# MEMORY.net
KiCad netlist of a schematic drawn in Altium Designer
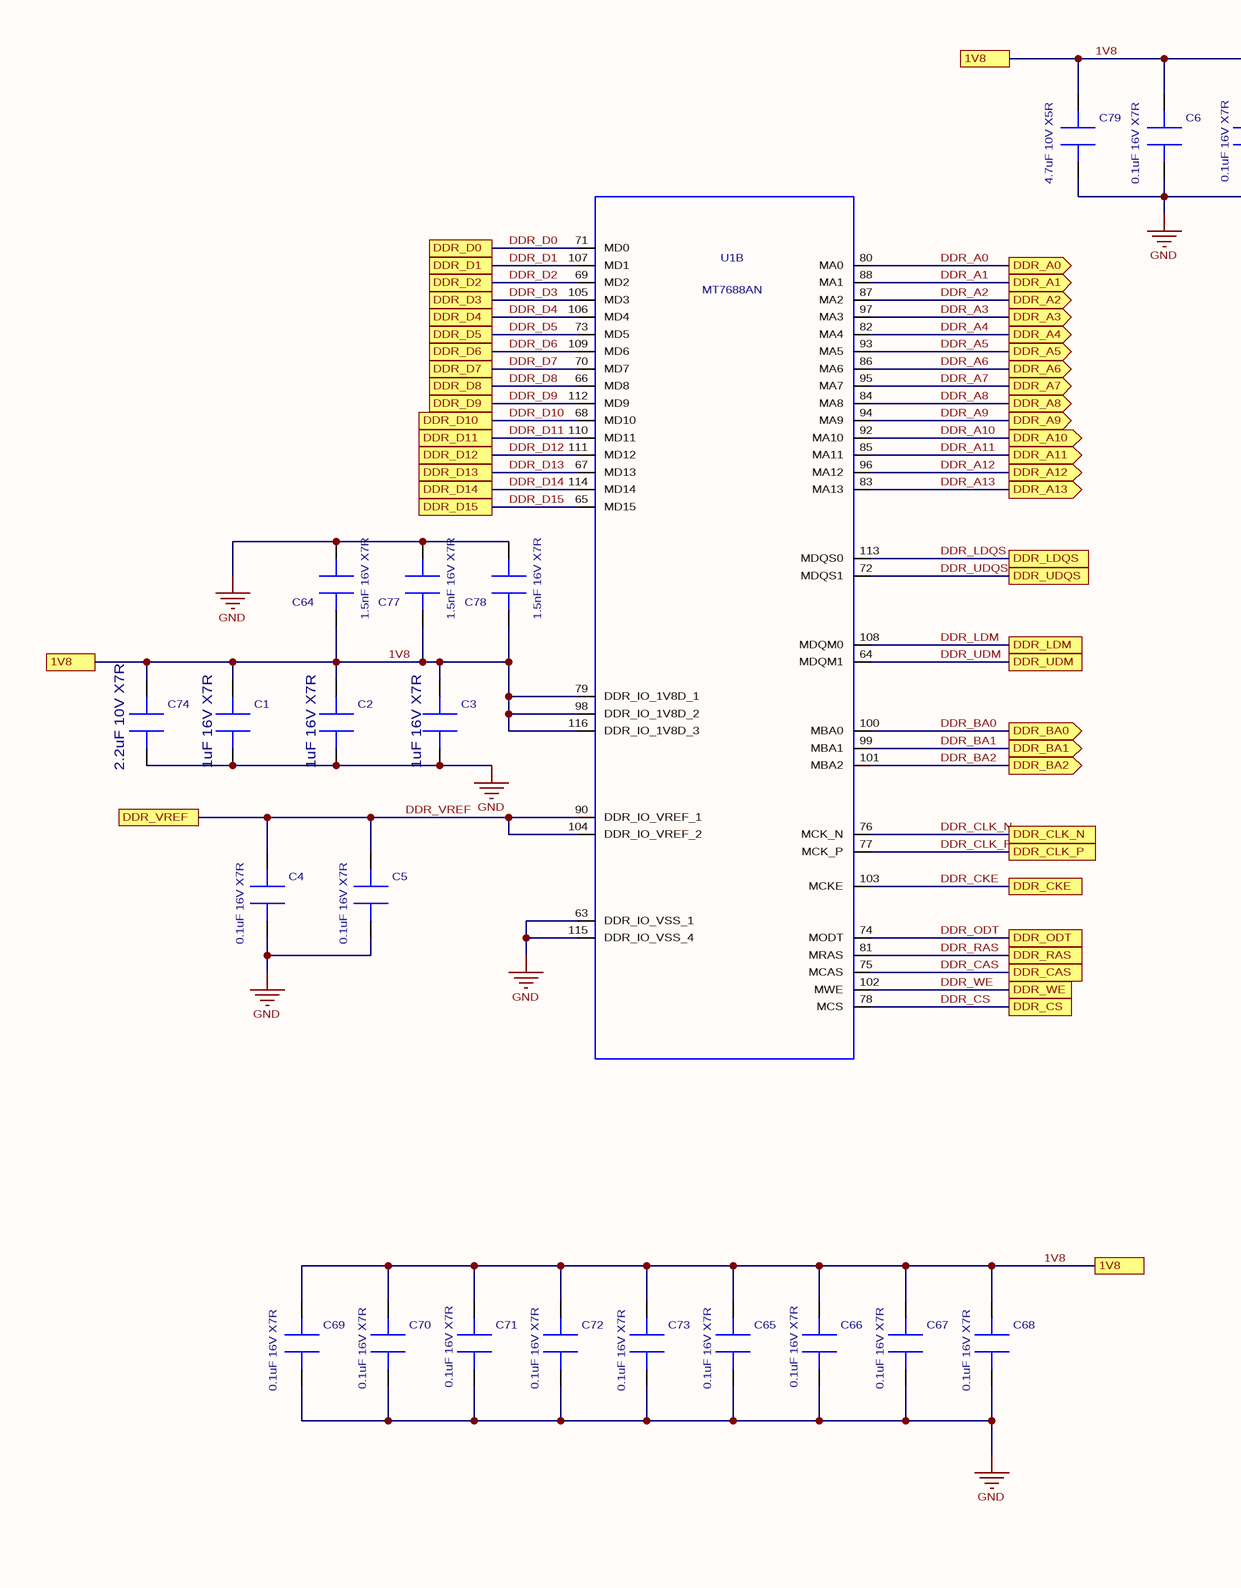
[diagram p0: MEMORY.SchDoc, left]
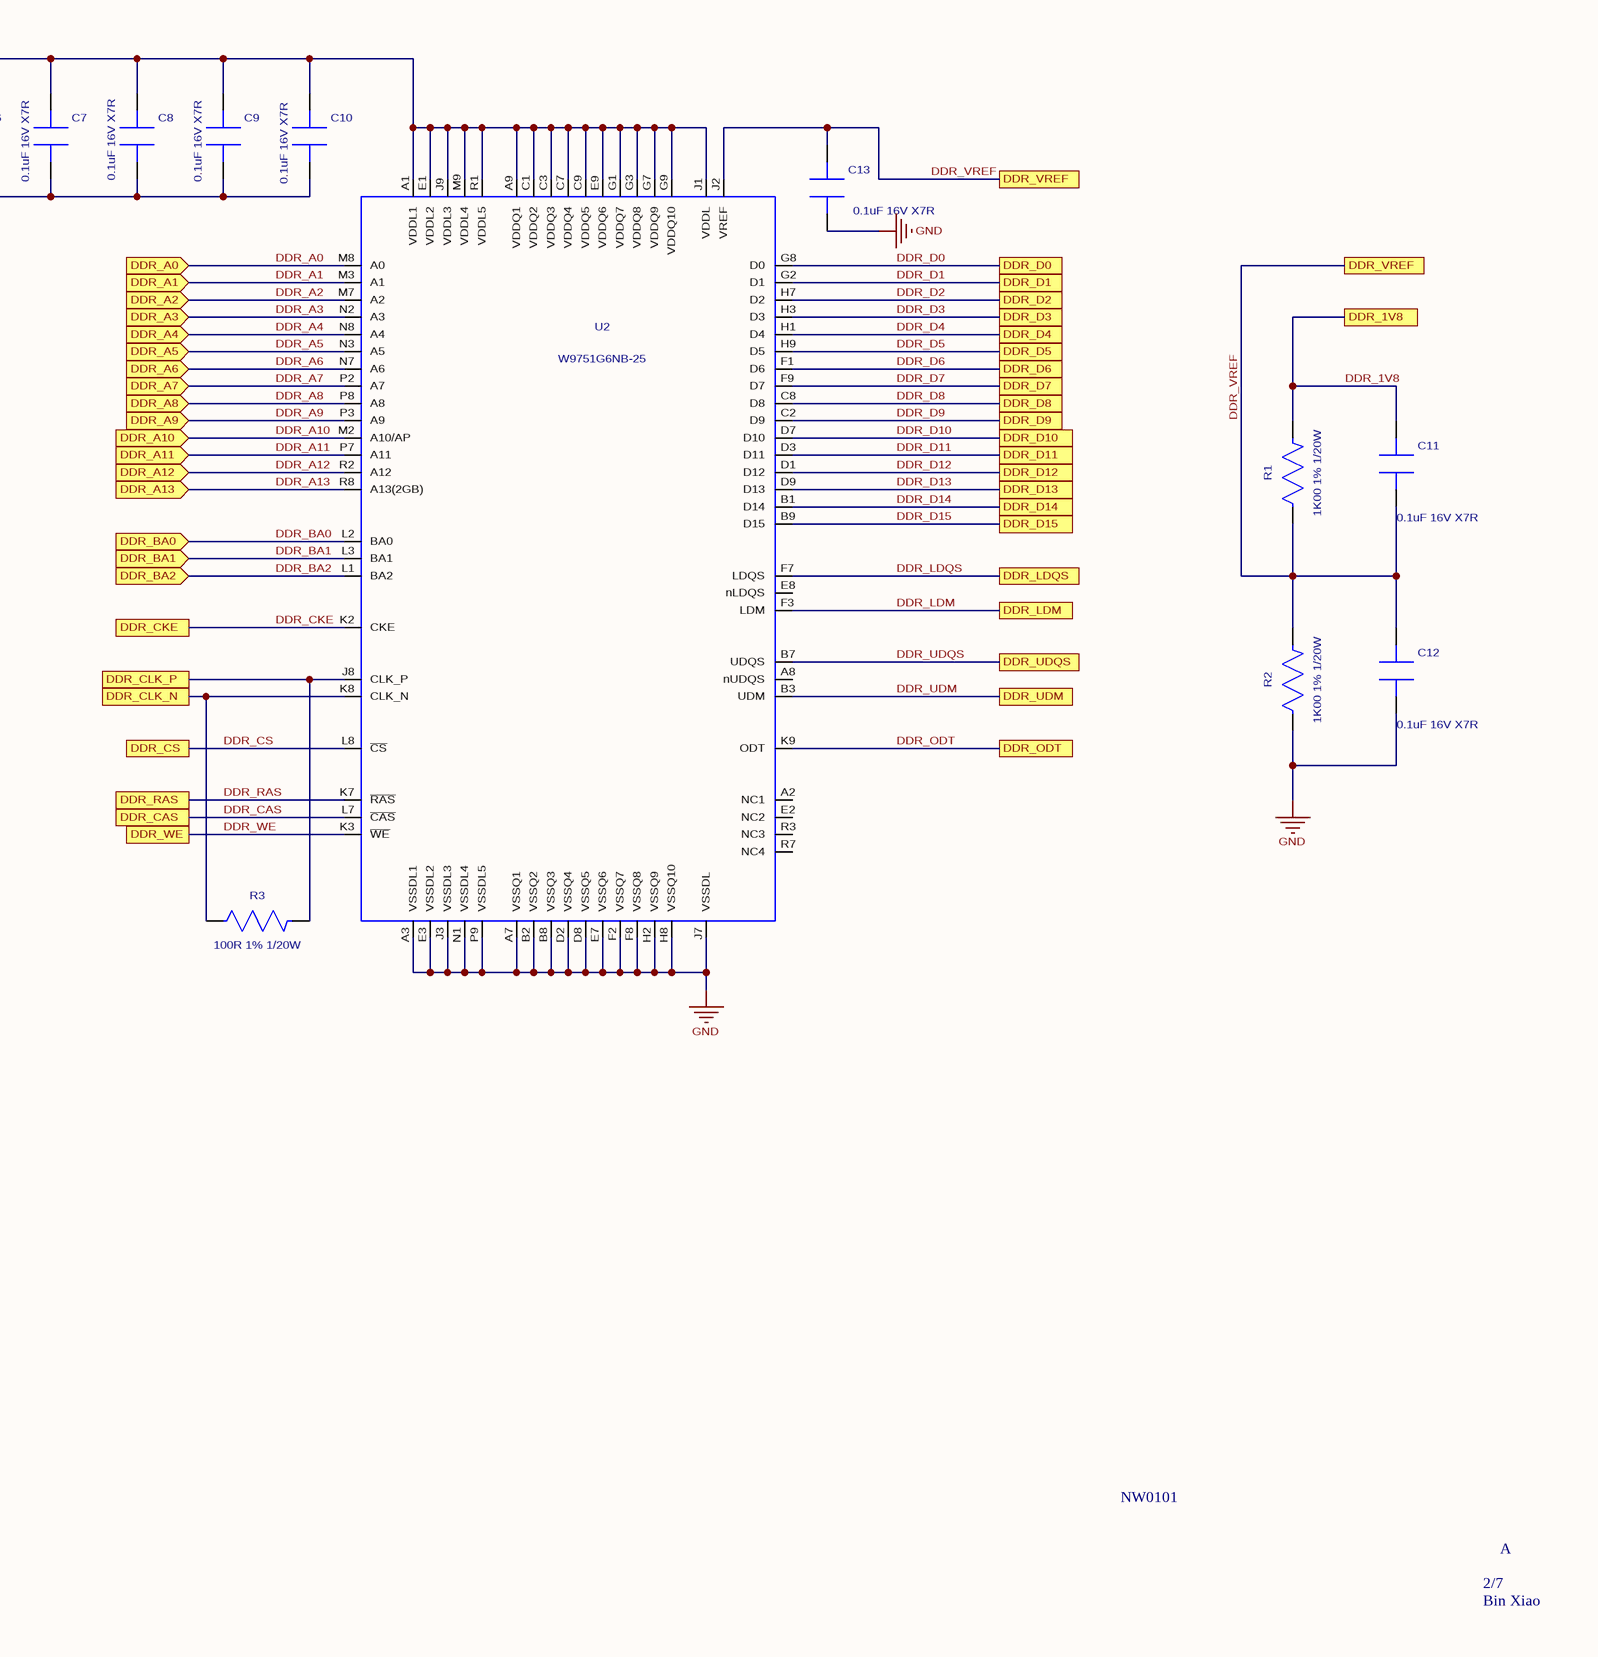
[diagram p1: MEMORY.SchDoc, right]

(export (version "E")
  (design (tool "Eeschema 10.0.6"))
  (components
    (comp (ref "C1")
      (value "1uF 16V X7R")
      (footprint "C0402")
      (description "CAP CER 1UF 6.3V X7R 0402")
      (fields
        (field (name "PART NUMBER") "GRM155R70J105KA12D")
        (field (name "MANUFACTURER") "Murata Electronics")
      )
      (libsource (lib "NetworkModule") (part "CAP0402-105-6.3V-X7R"))
    )
    (comp (ref "C2")
      (value "1uF 16V X7R")
      (footprint "C0402")
      (description "CAP CER 1UF 6.3V X7R 0402")
      (fields
        (field (name "PART NUMBER") "GRM155R70J105KA12D")
        (field (name "MANUFACTURER") "Murata Electronics")
      )
      (libsource (lib "NetworkModule") (part "CAP0402-105-6.3V-X7R"))
    )
    (comp (ref "C3")
      (value "1uF 16V X7R")
      (footprint "C0402")
      (description "CAP CER 1UF 6.3V X7R 0402")
      (fields
        (field (name "PART NUMBER") "GRM155R70J105KA12D")
        (field (name "MANUFACTURER") "Murata Electronics")
      )
      (libsource (lib "NetworkModule") (part "CAP0402-105-6.3V-X7R"))
    )
    (comp (ref "C4")
      (value "0.1uF 16V X7R")
      (footprint "C0201")
      (description "CAP CER 0.1UF 16V X7R 0201")
      (fields
        (field (name "PART NUMBER") "GRM033Z71C104KE14D")
        (field (name "MANUFACTURER") "Murata Electronics")
      )
      (libsource (lib "NetworkModule") (part "CAP0201-104-16V-X7R"))
    )
    (comp (ref "C5")
      (value "0.1uF 16V X7R")
      (footprint "C0201")
      (description "CAP CER 0.1UF 16V X7R 0201")
      (fields
        (field (name "PART NUMBER") "GRM033Z71C104KE14D")
        (field (name "MANUFACTURER") "Murata Electronics")
      )
      (libsource (lib "NetworkModule") (part "CAP0201-104-16V-X7R"))
    )
    (comp (ref "C6")
      (value "0.1uF 16V X7R")
      (footprint "C0201")
      (description "CAP CER 0.1UF 16V X7R 0201")
      (fields
        (field (name "PART NUMBER") "GRM033Z71C104KE14D")
        (field (name "MANUFACTURER") "Murata Electronics")
      )
      (libsource (lib "NetworkModule") (part "CAP0201-104-16V-X7R"))
    )
    (comp (ref "C7")
      (value "0.1uF 16V X7R")
      (footprint "C0201")
      (description "CAP CER 0.1UF 16V X7R 0201")
      (fields
        (field (name "PART NUMBER") "GRM033Z71C104KE14D")
        (field (name "MANUFACTURER") "Murata Electronics")
      )
      (libsource (lib "NetworkModule") (part "CAP0201-104-16V-X7R"))
    )
    (comp (ref "C8")
      (value "0.1uF 16V X7R")
      (footprint "C0201")
      (description "CAP CER 0.1UF 16V X7R 0201")
      (fields
        (field (name "PART NUMBER") "GRM033Z71C104KE14D")
        (field (name "MANUFACTURER") "Murata Electronics")
      )
      (libsource (lib "NetworkModule") (part "CAP0201-104-16V-X7R"))
    )
    (comp (ref "C9")
      (value "0.1uF 16V X7R")
      (footprint "C0201")
      (description "CAP CER 0.1UF 16V X7R 0201")
      (fields
        (field (name "PART NUMBER") "GRM033Z71C104KE14D")
        (field (name "MANUFACTURER") "Murata Electronics")
      )
      (libsource (lib "NetworkModule") (part "CAP0201-104-16V-X7R"))
    )
    (comp (ref "C10")
      (value "0.1uF 16V X7R")
      (footprint "C0201")
      (description "CAP CER 0.1UF 16V X7R 0201")
      (fields
        (field (name "PART NUMBER") "GRM033Z71C104KE14D")
        (field (name "MANUFACTURER") "Murata Electronics")
      )
      (libsource (lib "NetworkModule") (part "CAP0201-104-16V-X7R"))
    )
    (comp (ref "C11")
      (value "0.1uF 16V X7R")
      (footprint "C0201")
      (description "CAP CER 0.1UF 16V X7R 0201")
      (fields
        (field (name "PART NUMBER") "GRM033Z71C104KE14D")
        (field (name "MANUFACTURER") "Murata Electronics")
      )
      (libsource (lib "NetworkModule") (part "CAP0201-104-16V-X7R"))
    )
    (comp (ref "C12")
      (value "0.1uF 16V X7R")
      (footprint "C0201")
      (description "CAP CER 0.1UF 16V X7R 0201")
      (fields
        (field (name "PART NUMBER") "GRM033Z71C104KE14D")
        (field (name "MANUFACTURER") "Murata Electronics")
      )
      (libsource (lib "NetworkModule") (part "CAP0201-104-16V-X7R"))
    )
    (comp (ref "C13")
      (value "0.1uF 16V X7R")
      (footprint "C0201")
      (description "CAP CER 0.1UF 16V X7R 0201")
      (fields
        (field (name "PART NUMBER") "GRM033Z71C104KE14D")
        (field (name "MANUFACTURER") "Murata Electronics")
      )
      (libsource (lib "NetworkModule") (part "CAP0201-104-16V-X7R"))
    )
    (comp (ref "C64")
      (value "1.5nF 16V X7R")
      (footprint "C0201")
      (description "CAP CER 1500PF 16V X7R 0201")
      (fields
        (field (name "PART NUMBER") "CGA1A2X7R1C152K030BA")
        (field (name "MANUFACTURER") "TDK Corporation")
      )
      (libsource (lib "NetworkModule") (part "CAP0201-152-16V-X7R"))
    )
    (comp (ref "C65")
      (value "0.1uF 16V X7R")
      (footprint "C0201")
      (description "CAP CER 0.1UF 16V X7R 0201")
      (fields
        (field (name "PART NUMBER") "GRM033Z71C104KE14D")
        (field (name "MANUFACTURER") "Murata Electronics")
      )
      (libsource (lib "NetworkModule") (part "CAP0201-104-16V-X7R"))
    )
    (comp (ref "C66")
      (value "0.1uF 16V X7R")
      (footprint "C0201")
      (description "CAP CER 0.1UF 16V X7R 0201")
      (fields
        (field (name "PART NUMBER") "GRM033Z71C104KE14D")
        (field (name "MANUFACTURER") "Murata Electronics")
      )
      (libsource (lib "NetworkModule") (part "CAP0201-104-16V-X7R"))
    )
    (comp (ref "C67")
      (value "0.1uF 16V X7R")
      (footprint "C0201")
      (description "CAP CER 0.1UF 16V X7R 0201")
      (fields
        (field (name "PART NUMBER") "GRM033Z71C104KE14D")
        (field (name "MANUFACTURER") "Murata Electronics")
      )
      (libsource (lib "NetworkModule") (part "CAP0201-104-16V-X7R"))
    )
    (comp (ref "C68")
      (value "0.1uF 16V X7R")
      (footprint "C0201")
      (description "CAP CER 0.1UF 16V X7R 0201")
      (fields
        (field (name "PART NUMBER") "GRM033Z71C104KE14D")
        (field (name "MANUFACTURER") "Murata Electronics")
      )
      (libsource (lib "NetworkModule") (part "CAP0201-104-16V-X7R"))
    )
    (comp (ref "C69")
      (value "0.1uF 16V X7R")
      (footprint "C0201")
      (description "CAP CER 0.1UF 16V X7R 0201")
      (fields
        (field (name "PART NUMBER") "GRM033Z71C104KE14D")
        (field (name "MANUFACTURER") "Murata Electronics")
      )
      (libsource (lib "NetworkModule") (part "CAP0201-104-16V-X7R"))
    )
    (comp (ref "C70")
      (value "0.1uF 16V X7R")
      (footprint "C0201")
      (description "CAP CER 0.1UF 16V X7R 0201")
      (fields
        (field (name "PART NUMBER") "GRM033Z71C104KE14D")
        (field (name "MANUFACTURER") "Murata Electronics")
      )
      (libsource (lib "NetworkModule") (part "CAP0201-104-16V-X7R"))
    )
    (comp (ref "C71")
      (value "0.1uF 16V X7R")
      (footprint "C0201")
      (description "CAP CER 0.1UF 16V X7R 0201")
      (fields
        (field (name "PART NUMBER") "GRM033Z71C104KE14D")
        (field (name "MANUFACTURER") "Murata Electronics")
      )
      (libsource (lib "NetworkModule") (part "CAP0201-104-16V-X7R"))
    )
    (comp (ref "C72")
      (value "0.1uF 16V X7R")
      (footprint "C0201")
      (description "CAP CER 0.1UF 16V X7R 0201")
      (fields
        (field (name "PART NUMBER") "GRM033Z71C104KE14D")
        (field (name "MANUFACTURER") "Murata Electronics")
      )
      (libsource (lib "NetworkModule") (part "CAP0201-104-16V-X7R"))
    )
    (comp (ref "C73")
      (value "0.1uF 16V X7R")
      (footprint "C0201")
      (description "CAP CER 0.1UF 16V X7R 0201")
      (fields
        (field (name "PART NUMBER") "GRM033Z71C104KE14D")
        (field (name "MANUFACTURER") "Murata Electronics")
      )
      (libsource (lib "NetworkModule") (part "CAP0201-104-16V-X7R"))
    )
    (comp (ref "C74")
      (value "2.2uF 10V X7R")
      (footprint "C0402")
      (description "CAP CER 2.2UF 10V X7R 0402")
      (fields
        (field (name "PART NUMBER") "GRM155Z71A225KE01D")
        (field (name "MANUFACTURER") "Murata Electronics")
      )
      (libsource (lib "NetworkModule") (part "CAP0402-225-6.3V-X7R"))
    )
    (comp (ref "C77")
      (value "1.5nF 16V X7R")
      (footprint "C0201")
      (description "CAP CER 1500PF 16V X7R 0201")
      (fields
        (field (name "PART NUMBER") "CGA1A2X7R1C152K030BA")
        (field (name "MANUFACTURER") "TDK Corporation")
      )
      (libsource (lib "NetworkModule") (part "CAP0201-152-16V-X7R"))
    )
    (comp (ref "C78")
      (value "1.5nF 16V X7R")
      (footprint "C0201")
      (description "CAP CER 1500PF 16V X7R 0201")
      (fields
        (field (name "PART NUMBER") "CGA1A2X7R1C152K030BA")
        (field (name "MANUFACTURER") "TDK Corporation")
      )
      (libsource (lib "NetworkModule") (part "CAP0201-152-16V-X7R"))
    )
    (comp (ref "C79")
      (value "4.7uF 10V X5R")
      (footprint "C0402")
      (description "CAP CER 4.7UF 10V X5R 0402")
      (fields
        (field (name "PART NUMBER") "CL05A475MP5NRNC")
        (field (name "MANUFACTURER") "Samsung Electro-Mechanics")
      )
      (libsource (lib "NetworkModule") (part "CAP0402-475-10V-X5R"))
    )
    (comp (ref "R1")
      (value "1K00 1% 1/20W")
      (footprint "R0201")
      (description "RES 1K OHM 1% 1/20W 0201")
      (fields
        (field (name "PART NUMBER") "RMCF0201FT1K00")
        (field (name "MANUFACTURER") "Stackpole Electronics Inc")
      )
      (libsource (lib "NetworkModule") (part "RES0201-1K00"))
    )
    (comp (ref "R2")
      (value "1K00 1% 1/20W")
      (footprint "R0201")
      (description "RES 1K OHM 1% 1/20W 0201")
      (fields
        (field (name "PART NUMBER") "RMCF0201FT1K00")
        (field (name "MANUFACTURER") "Stackpole Electronics Inc")
      )
      (libsource (lib "NetworkModule") (part "RES0201-1K00"))
    )
    (comp (ref "R3")
      (value "100R 1% 1/20W")
      (footprint "R0201")
      (description "RES 100 OHM 1% 1/20W 0201")
      (fields (field (name "MANUFACTURER") "Yageo") (field (name "PART NUMBER") "RC0201FR-07100RL"))
      (libsource (lib "NetworkModule") (part "RES0201-100R"))
    )
    (comp (ref "U1")
      (value "MT7688AN")
      (footprint "DR-QFN-128")
      (description "580Mhz 32bits Networking Processor")
      (fields (field (name "MANUFACTURER") "MediaTek Inc"))
      (libsource (lib "*") (part "MT7688AN"))
    )
    (comp (ref "U2")
      (value "W9751G6NB-25")
      (footprint "TWBGA-84_8X12P5_ISI")
      (description "IC DRAM 512MBIT PARALLEL 84VFBGA")
      (fields (field (name "MANUFACTURER") "Winbond Electronics"))
      (libsource (lib "NetworkModule") (part "W9751G6NB-25"))
    )
  )
  (nets
    (net (code "1") (name "/1V8") (class "Default")
      (node (ref "C1") (pin "1") (pinfunction "1_1") (pintype "passive"))
      (node (ref "C10") (pin "1") (pinfunction "1_1") (pintype "passive"))
      (node (ref "C2") (pin "1") (pinfunction "1_1") (pintype "passive"))
      (node (ref "C3") (pin "1") (pinfunction "1_1") (pintype "passive"))
      (node (ref "C6") (pin "1") (pinfunction "1_1") (pintype "passive"))
      (node (ref "C64") (pin "1") (pinfunction "1_1") (pintype "passive"))
      (node (ref "C65") (pin "1") (pinfunction "1_1") (pintype "passive"))
      (node (ref "C66") (pin "1") (pinfunction "1_1") (pintype "passive"))
      (node (ref "C67") (pin "1") (pinfunction "1_1") (pintype "passive"))
      (node (ref "C68") (pin "1") (pinfunction "1_1") (pintype "passive"))
      (node (ref "C69") (pin "1") (pinfunction "1_1") (pintype "passive"))
      (node (ref "C7") (pin "1") (pinfunction "1_1") (pintype "passive"))
      (node (ref "C70") (pin "1") (pinfunction "1_1") (pintype "passive"))
      (node (ref "C71") (pin "1") (pinfunction "1_1") (pintype "passive"))
      (node (ref "C72") (pin "1") (pinfunction "1_1") (pintype "passive"))
      (node (ref "C73") (pin "1") (pinfunction "1_1") (pintype "passive"))
      (node (ref "C74") (pin "1") (pinfunction "1_1") (pintype "passive"))
      (node (ref "C77") (pin "1") (pinfunction "1_1") (pintype "passive"))
      (node (ref "C78") (pin "1") (pinfunction "1_1") (pintype "passive"))
      (node (ref "C79") (pin "1") (pinfunction "1_1") (pintype "passive"))
      (node (ref "C8") (pin "1") (pinfunction "1_1") (pintype "passive"))
      (node (ref "C9") (pin "1") (pinfunction "1_1") (pintype "passive"))
      (node (ref "U1") (pin "116") (pinfunction "DDR_IO_1V8D_3_116") (pintype "passive"))
      (node (ref "U1") (pin "79") (pinfunction "DDR_IO_1V8D_1_79") (pintype "passive"))
      (node (ref "U1") (pin "98") (pinfunction "DDR_IO_1V8D_2_98") (pintype "passive"))
      (node (ref "U2") (pin "A1") (pinfunction "VDDL1_A1") (pintype "passive"))
      (node (ref "U2") (pin "A9") (pinfunction "VDDQ1_A9") (pintype "passive"))
      (node (ref "U2") (pin "C1") (pinfunction "VDDQ2_C1") (pintype "passive"))
      (node (ref "U2") (pin "C3") (pinfunction "VDDQ3_C3") (pintype "passive"))
      (node (ref "U2") (pin "C7") (pinfunction "VDDQ4_C7") (pintype "passive"))
      (node (ref "U2") (pin "C9") (pinfunction "VDDQ5_C9") (pintype "passive"))
      (node (ref "U2") (pin "E1") (pinfunction "VDDL2_E1") (pintype "passive"))
      (node (ref "U2") (pin "E9") (pinfunction "VDDQ6_E9") (pintype "passive"))
      (node (ref "U2") (pin "G1") (pinfunction "VDDQ7_G1") (pintype "passive"))
      (node (ref "U2") (pin "G3") (pinfunction "VDDQ8_G3") (pintype "passive"))
      (node (ref "U2") (pin "G7") (pinfunction "VDDQ9_G7") (pintype "passive"))
      (node (ref "U2") (pin "G9") (pinfunction "VDDQ10_G9") (pintype "passive"))
      (node (ref "U2") (pin "J1") (pinfunction "VDDL_J1") (pintype "passive"))
      (node (ref "U2") (pin "J9") (pinfunction "VDDL3_J9") (pintype "passive"))
      (node (ref "U2") (pin "M9") (pinfunction "VDDL4_M9") (pintype "passive"))
      (node (ref "U2") (pin "R1") (pinfunction "VDDL5_R1") (pintype "passive"))
    )
    (net (code "2") (name "/DDR_1V8") (class "Default")
      (node (ref "C11") (pin "1") (pinfunction "1_1") (pintype "passive"))
      (node (ref "R1") (pin "2") (pinfunction "2_2") (pintype "passive"))
    )
    (net (code "3") (name "/DDR_A0") (class "Default")
      (node (ref "U1") (pin "80") (pinfunction "MA0_80") (pintype "passive"))
      (node (ref "U2") (pin "M8") (pinfunction "A0_M8") (pintype "passive"))
    )
    (net (code "4") (name "/DDR_A1") (class "Default")
      (node (ref "U1") (pin "88") (pinfunction "MA1_88") (pintype "passive"))
      (node (ref "U2") (pin "M3") (pinfunction "A1_M3") (pintype "passive"))
    )
    (net (code "5") (name "/DDR_A2") (class "Default")
      (node (ref "U1") (pin "87") (pinfunction "MA2_87") (pintype "passive"))
      (node (ref "U2") (pin "M7") (pinfunction "A2_M7") (pintype "passive"))
    )
    (net (code "6") (name "/DDR_A3") (class "Default")
      (node (ref "U1") (pin "97") (pinfunction "MA3_97") (pintype "passive"))
      (node (ref "U2") (pin "N2") (pinfunction "A3_N2") (pintype "passive"))
    )
    (net (code "7") (name "/DDR_A4") (class "Default")
      (node (ref "U1") (pin "82") (pinfunction "MA4_82") (pintype "passive"))
      (node (ref "U2") (pin "N8") (pinfunction "A4_N8") (pintype "passive"))
    )
    (net (code "8") (name "/DDR_A5") (class "Default")
      (node (ref "U1") (pin "93") (pinfunction "MA5_93") (pintype "passive"))
      (node (ref "U2") (pin "N3") (pinfunction "A5_N3") (pintype "passive"))
    )
    (net (code "9") (name "/DDR_A6") (class "Default")
      (node (ref "U1") (pin "86") (pinfunction "MA6_86") (pintype "passive"))
      (node (ref "U2") (pin "N7") (pinfunction "A6_N7") (pintype "passive"))
    )
    (net (code "10") (name "/DDR_A7") (class "Default")
      (node (ref "U1") (pin "95") (pinfunction "MA7_95") (pintype "passive"))
      (node (ref "U2") (pin "P2") (pinfunction "A7_P2") (pintype "passive"))
    )
    (net (code "11") (name "/DDR_A8") (class "Default")
      (node (ref "U1") (pin "84") (pinfunction "MA8_84") (pintype "passive"))
      (node (ref "U2") (pin "P8") (pinfunction "A8_P8") (pintype "passive"))
    )
    (net (code "12") (name "/DDR_A9") (class "Default")
      (node (ref "U1") (pin "94") (pinfunction "MA9_94") (pintype "passive"))
      (node (ref "U2") (pin "P3") (pinfunction "A9_P3") (pintype "passive"))
    )
    (net (code "13") (name "/DDR_A10") (class "Default")
      (node (ref "U1") (pin "92") (pinfunction "MA10_92") (pintype "passive"))
      (node (ref "U2") (pin "M2") (pinfunction "A10/AP_M2") (pintype "passive"))
    )
    (net (code "14") (name "/DDR_A11") (class "Default")
      (node (ref "U1") (pin "85") (pinfunction "MA11_85") (pintype "passive"))
      (node (ref "U2") (pin "P7") (pinfunction "A11_P7") (pintype "passive"))
    )
    (net (code "15") (name "/DDR_A12") (class "Default")
      (node (ref "U1") (pin "96") (pinfunction "MA12_96") (pintype "passive"))
      (node (ref "U2") (pin "R2") (pinfunction "A12_R2") (pintype "passive"))
    )
    (net (code "16") (name "/DDR_A13") (class "Default")
      (node (ref "U1") (pin "83") (pinfunction "MA13_83") (pintype "passive"))
      (node (ref "U2") (pin "R8") (pinfunction "A13(2GB)_R8") (pintype "passive"))
    )
    (net (code "17") (name "/DDR_BA0") (class "Default")
      (node (ref "U1") (pin "100") (pinfunction "MBA0_100") (pintype "passive"))
      (node (ref "U2") (pin "L2") (pinfunction "BA0_L2") (pintype "passive"))
    )
    (net (code "18") (name "/DDR_BA1") (class "Default")
      (node (ref "U1") (pin "99") (pinfunction "MBA1_99") (pintype "passive"))
      (node (ref "U2") (pin "L3") (pinfunction "BA1_L3") (pintype "passive"))
    )
    (net (code "19") (name "/DDR_BA2") (class "Default")
      (node (ref "U1") (pin "101") (pinfunction "MBA2_101") (pintype "passive"))
      (node (ref "U2") (pin "L1") (pinfunction "BA2_L1") (pintype "passive"))
    )
    (net (code "20") (name "/DDR_CAS") (class "Default")
      (node (ref "U1") (pin "75") (pinfunction "MCAS_75") (pintype "passive"))
      (node (ref "U2") (pin "L7") (pinfunction "CAS_L7") (pintype "passive"))
    )
    (net (code "21") (name "/DDR_CKE") (class "Default")
      (node (ref "U1") (pin "103") (pinfunction "MCKE_103") (pintype "passive"))
      (node (ref "U2") (pin "K2") (pinfunction "CKE_K2") (pintype "passive"))
    )
    (net (code "22") (name "/DDR_CLK_N") (class "Default")
      (node (ref "R3") (pin "1") (pinfunction "1_1") (pintype "passive"))
      (node (ref "U1") (pin "76") (pinfunction "MCK_N_76") (pintype "passive"))
      (node (ref "U2") (pin "K8") (pinfunction "CLK_N_K8") (pintype "passive"))
    )
    (net (code "23") (name "/DDR_CLK_P") (class "Default")
      (node (ref "R3") (pin "2") (pinfunction "2_2") (pintype "passive"))
      (node (ref "U1") (pin "77") (pinfunction "MCK_P_77") (pintype "passive"))
      (node (ref "U2") (pin "J8") (pinfunction "CLK_P_J8") (pintype "passive"))
    )
    (net (code "24") (name "/DDR_CS") (class "Default")
      (node (ref "U1") (pin "78") (pinfunction "MCS_78") (pintype "passive"))
      (node (ref "U2") (pin "L8") (pinfunction "CS_L8") (pintype "passive"))
    )
    (net (code "25") (name "/DDR_D0") (class "Default")
      (node (ref "U1") (pin "71") (pinfunction "MD0_71") (pintype "passive"))
      (node (ref "U2") (pin "G8") (pinfunction "D0_G8") (pintype "passive"))
    )
    (net (code "26") (name "/DDR_D1") (class "Default")
      (node (ref "U1") (pin "107") (pinfunction "MD1_107") (pintype "passive"))
      (node (ref "U2") (pin "G2") (pinfunction "D1_G2") (pintype "passive"))
    )
    (net (code "27") (name "/DDR_D2") (class "Default")
      (node (ref "U1") (pin "69") (pinfunction "MD2_69") (pintype "passive"))
      (node (ref "U2") (pin "H7") (pinfunction "D2_H7") (pintype "passive"))
    )
    (net (code "28") (name "/DDR_D3") (class "Default")
      (node (ref "U1") (pin "105") (pinfunction "MD3_105") (pintype "passive"))
      (node (ref "U2") (pin "H3") (pinfunction "D3_H3") (pintype "passive"))
    )
    (net (code "29") (name "/DDR_D4") (class "Default")
      (node (ref "U1") (pin "106") (pinfunction "MD4_106") (pintype "passive"))
      (node (ref "U2") (pin "H1") (pinfunction "D4_H1") (pintype "passive"))
    )
    (net (code "30") (name "/DDR_D5") (class "Default")
      (node (ref "U1") (pin "73") (pinfunction "MD5_73") (pintype "passive"))
      (node (ref "U2") (pin "H9") (pinfunction "D5_H9") (pintype "passive"))
    )
    (net (code "31") (name "/DDR_D6") (class "Default")
      (node (ref "U1") (pin "109") (pinfunction "MD6_109") (pintype "passive"))
      (node (ref "U2") (pin "F1") (pinfunction "D6_F1") (pintype "passive"))
    )
    (net (code "32") (name "/DDR_D7") (class "Default")
      (node (ref "U1") (pin "70") (pinfunction "MD7_70") (pintype "passive"))
      (node (ref "U2") (pin "F9") (pinfunction "D7_F9") (pintype "passive"))
    )
    (net (code "33") (name "/DDR_D8") (class "Default")
      (node (ref "U1") (pin "66") (pinfunction "MD8_66") (pintype "passive"))
      (node (ref "U2") (pin "C8") (pinfunction "D8_C8") (pintype "passive"))
    )
    (net (code "34") (name "/DDR_D9") (class "Default")
      (node (ref "U1") (pin "112") (pinfunction "MD9_112") (pintype "passive"))
      (node (ref "U2") (pin "C2") (pinfunction "D9_C2") (pintype "passive"))
    )
    (net (code "35") (name "/DDR_D10") (class "Default")
      (node (ref "U1") (pin "68") (pinfunction "MD10_68") (pintype "passive"))
      (node (ref "U2") (pin "D7") (pinfunction "D10_D7") (pintype "passive"))
    )
    (net (code "36") (name "/DDR_D11") (class "Default")
      (node (ref "U1") (pin "110") (pinfunction "MD11_110") (pintype "passive"))
      (node (ref "U2") (pin "D3") (pinfunction "D11_D3") (pintype "passive"))
    )
    (net (code "37") (name "/DDR_D12") (class "Default")
      (node (ref "U1") (pin "111") (pinfunction "MD12_111") (pintype "passive"))
      (node (ref "U2") (pin "D1") (pinfunction "D12_D1") (pintype "passive"))
    )
    (net (code "38") (name "/DDR_D13") (class "Default")
      (node (ref "U1") (pin "67") (pinfunction "MD13_67") (pintype "passive"))
      (node (ref "U2") (pin "D9") (pinfunction "D13_D9") (pintype "passive"))
    )
    (net (code "39") (name "/DDR_D14") (class "Default")
      (node (ref "U1") (pin "114") (pinfunction "MD14_114") (pintype "passive"))
      (node (ref "U2") (pin "B1") (pinfunction "D14_B1") (pintype "passive"))
    )
    (net (code "40") (name "/DDR_D15") (class "Default")
      (node (ref "U1") (pin "65") (pinfunction "MD15_65") (pintype "passive"))
      (node (ref "U2") (pin "B9") (pinfunction "D15_B9") (pintype "passive"))
    )
    (net (code "41") (name "/DDR_LDM") (class "Default")
      (node (ref "U1") (pin "108") (pinfunction "MDQM0_108") (pintype "passive"))
      (node (ref "U2") (pin "F3") (pinfunction "LDM_F3") (pintype "passive"))
    )
    (net (code "42") (name "/DDR_LDQS") (class "Default")
      (node (ref "U1") (pin "113") (pinfunction "MDQS0_113") (pintype "passive"))
      (node (ref "U2") (pin "F7") (pinfunction "LDQS_F7") (pintype "passive"))
    )
    (net (code "43") (name "/DDR_ODT") (class "Default")
      (node (ref "U1") (pin "74") (pinfunction "MODT_74") (pintype "passive"))
      (node (ref "U2") (pin "K9") (pinfunction "ODT_K9") (pintype "passive"))
    )
    (net (code "44") (name "/DDR_RAS") (class "Default")
      (node (ref "U1") (pin "81") (pinfunction "MRAS_81") (pintype "passive"))
      (node (ref "U2") (pin "K7") (pinfunction "RAS_K7") (pintype "passive"))
    )
    (net (code "45") (name "/DDR_UDM") (class "Default")
      (node (ref "U1") (pin "64") (pinfunction "MDQM1_64") (pintype "passive"))
      (node (ref "U2") (pin "B3") (pinfunction "UDM_B3") (pintype "passive"))
    )
    (net (code "46") (name "/DDR_UDQS") (class "Default")
      (node (ref "U1") (pin "72") (pinfunction "MDQS1_72") (pintype "passive"))
      (node (ref "U2") (pin "B7") (pinfunction "UDQS_B7") (pintype "passive"))
    )
    (net (code "47") (name "/DDR_VREF") (class "Default")
      (node (ref "C11") (pin "2") (pinfunction "2_2") (pintype "passive"))
      (node (ref "C12") (pin "1") (pinfunction "1_1") (pintype "passive"))
      (node (ref "C13") (pin "1") (pinfunction "1_1") (pintype "passive"))
      (node (ref "C4") (pin "1") (pinfunction "1_1") (pintype "passive"))
      (node (ref "C5") (pin "1") (pinfunction "1_1") (pintype "passive"))
      (node (ref "R1") (pin "1") (pinfunction "1_1") (pintype "passive"))
      (node (ref "R2") (pin "2") (pinfunction "2_2") (pintype "passive"))
      (node (ref "U1") (pin "104") (pinfunction "DDR_IO_VREF_2_104") (pintype "passive"))
      (node (ref "U1") (pin "90") (pinfunction "DDR_IO_VREF_1_90") (pintype "passive"))
      (node (ref "U2") (pin "J2") (pinfunction "VREF_J2") (pintype "passive"))
    )
    (net (code "48") (name "/DDR_WE") (class "Default")
      (node (ref "U1") (pin "102") (pinfunction "MWE_102") (pintype "passive"))
      (node (ref "U2") (pin "K3") (pinfunction "WE_K3") (pintype "passive"))
    )
    (net (code "49") (name "GND") (class "Default")
      (node (ref "C1") (pin "2") (pinfunction "2_2") (pintype "passive"))
      (node (ref "C10") (pin "2") (pinfunction "2_2") (pintype "passive"))
      (node (ref "C12") (pin "2") (pinfunction "2_2") (pintype "passive"))
      (node (ref "C13") (pin "2") (pinfunction "2_2") (pintype "passive"))
      (node (ref "C2") (pin "2") (pinfunction "2_2") (pintype "passive"))
      (node (ref "C3") (pin "2") (pinfunction "2_2") (pintype "passive"))
      (node (ref "C4") (pin "2") (pinfunction "2_2") (pintype "passive"))
      (node (ref "C5") (pin "2") (pinfunction "2_2") (pintype "passive"))
      (node (ref "C6") (pin "2") (pinfunction "2_2") (pintype "passive"))
      (node (ref "C64") (pin "2") (pinfunction "2_2") (pintype "passive"))
      (node (ref "C65") (pin "2") (pinfunction "2_2") (pintype "passive"))
      (node (ref "C66") (pin "2") (pinfunction "2_2") (pintype "passive"))
      (node (ref "C67") (pin "2") (pinfunction "2_2") (pintype "passive"))
      (node (ref "C68") (pin "2") (pinfunction "2_2") (pintype "passive"))
      (node (ref "C69") (pin "2") (pinfunction "2_2") (pintype "passive"))
      (node (ref "C7") (pin "2") (pinfunction "2_2") (pintype "passive"))
      (node (ref "C70") (pin "2") (pinfunction "2_2") (pintype "passive"))
      (node (ref "C71") (pin "2") (pinfunction "2_2") (pintype "passive"))
      (node (ref "C72") (pin "2") (pinfunction "2_2") (pintype "passive"))
      (node (ref "C73") (pin "2") (pinfunction "2_2") (pintype "passive"))
      (node (ref "C74") (pin "2") (pinfunction "2_2") (pintype "passive"))
      (node (ref "C77") (pin "2") (pinfunction "2_2") (pintype "passive"))
      (node (ref "C78") (pin "2") (pinfunction "2_2") (pintype "passive"))
      (node (ref "C79") (pin "2") (pinfunction "2_2") (pintype "passive"))
      (node (ref "C8") (pin "2") (pinfunction "2_2") (pintype "passive"))
      (node (ref "C9") (pin "2") (pinfunction "2_2") (pintype "passive"))
      (node (ref "R2") (pin "1") (pinfunction "1_1") (pintype "passive"))
      (node (ref "U1") (pin "115") (pinfunction "DDR_IO_VSS_4_115") (pintype "passive"))
      (node (ref "U1") (pin "63") (pinfunction "DDR_IO_VSS_1_63") (pintype "passive"))
      (node (ref "U2") (pin "A3") (pinfunction "VSSDL1_A3") (pintype "passive"))
      (node (ref "U2") (pin "A7") (pinfunction "VSSQ1_A7") (pintype "passive"))
      (node (ref "U2") (pin "B2") (pinfunction "VSSQ2_B2") (pintype "passive"))
      (node (ref "U2") (pin "B8") (pinfunction "VSSQ3_B8") (pintype "passive"))
      (node (ref "U2") (pin "D2") (pinfunction "VSSQ4_D2") (pintype "passive"))
      (node (ref "U2") (pin "D8") (pinfunction "VSSQ5_D8") (pintype "passive"))
      (node (ref "U2") (pin "E3") (pinfunction "VSSDL2_E3") (pintype "passive"))
      (node (ref "U2") (pin "E7") (pinfunction "VSSQ6_E7") (pintype "passive"))
      (node (ref "U2") (pin "F2") (pinfunction "VSSQ7_F2") (pintype "passive"))
      (node (ref "U2") (pin "F8") (pinfunction "VSSQ8_F8") (pintype "passive"))
      (node (ref "U2") (pin "H2") (pinfunction "VSSQ9_H2") (pintype "passive"))
      (node (ref "U2") (pin "H8") (pinfunction "VSSQ10_H8") (pintype "passive"))
      (node (ref "U2") (pin "J3") (pinfunction "VSSDL3_J3") (pintype "passive"))
      (node (ref "U2") (pin "J7") (pinfunction "VSSDL_J7") (pintype "passive"))
      (node (ref "U2") (pin "N1") (pinfunction "VSSDL4_N1") (pintype "passive"))
      (node (ref "U2") (pin "P9") (pinfunction "VSSDL5_P9") (pintype "passive"))
    )
    (net (code "50") (name "unconnected-(U2-NC1-PadA2)") (class "Default")
      (node (ref "U2") (pin "A2") (pinfunction "NC1_A2") (pintype "passive"))
    )
    (net (code "51") (name "unconnected-(U2-NC2-PadE2)") (class "Default")
      (node (ref "U2") (pin "E2") (pinfunction "NC2_E2") (pintype "passive"))
    )
    (net (code "52") (name "unconnected-(U2-NC3-PadR3)") (class "Default")
      (node (ref "U2") (pin "R3") (pinfunction "NC3_R3") (pintype "passive"))
    )
    (net (code "53") (name "unconnected-(U2-NC4-PadR7)") (class "Default")
      (node (ref "U2") (pin "R7") (pinfunction "NC4_R7") (pintype "passive"))
    )
    (net (code "54") (name "unconnected-(U2-nLDQS-PadE8)") (class "Default")
      (node (ref "U2") (pin "E8") (pinfunction "nLDQS_E8") (pintype "passive"))
    )
    (net (code "55") (name "unconnected-(U2-nUDQS-PadA8)") (class "Default")
      (node (ref "U2") (pin "A8") (pinfunction "nUDQS_A8") (pintype "passive"))
    )
  )
)
